# Game_Consol_Power.net
KiCad netlist of a schematic drawn in Altium Designer
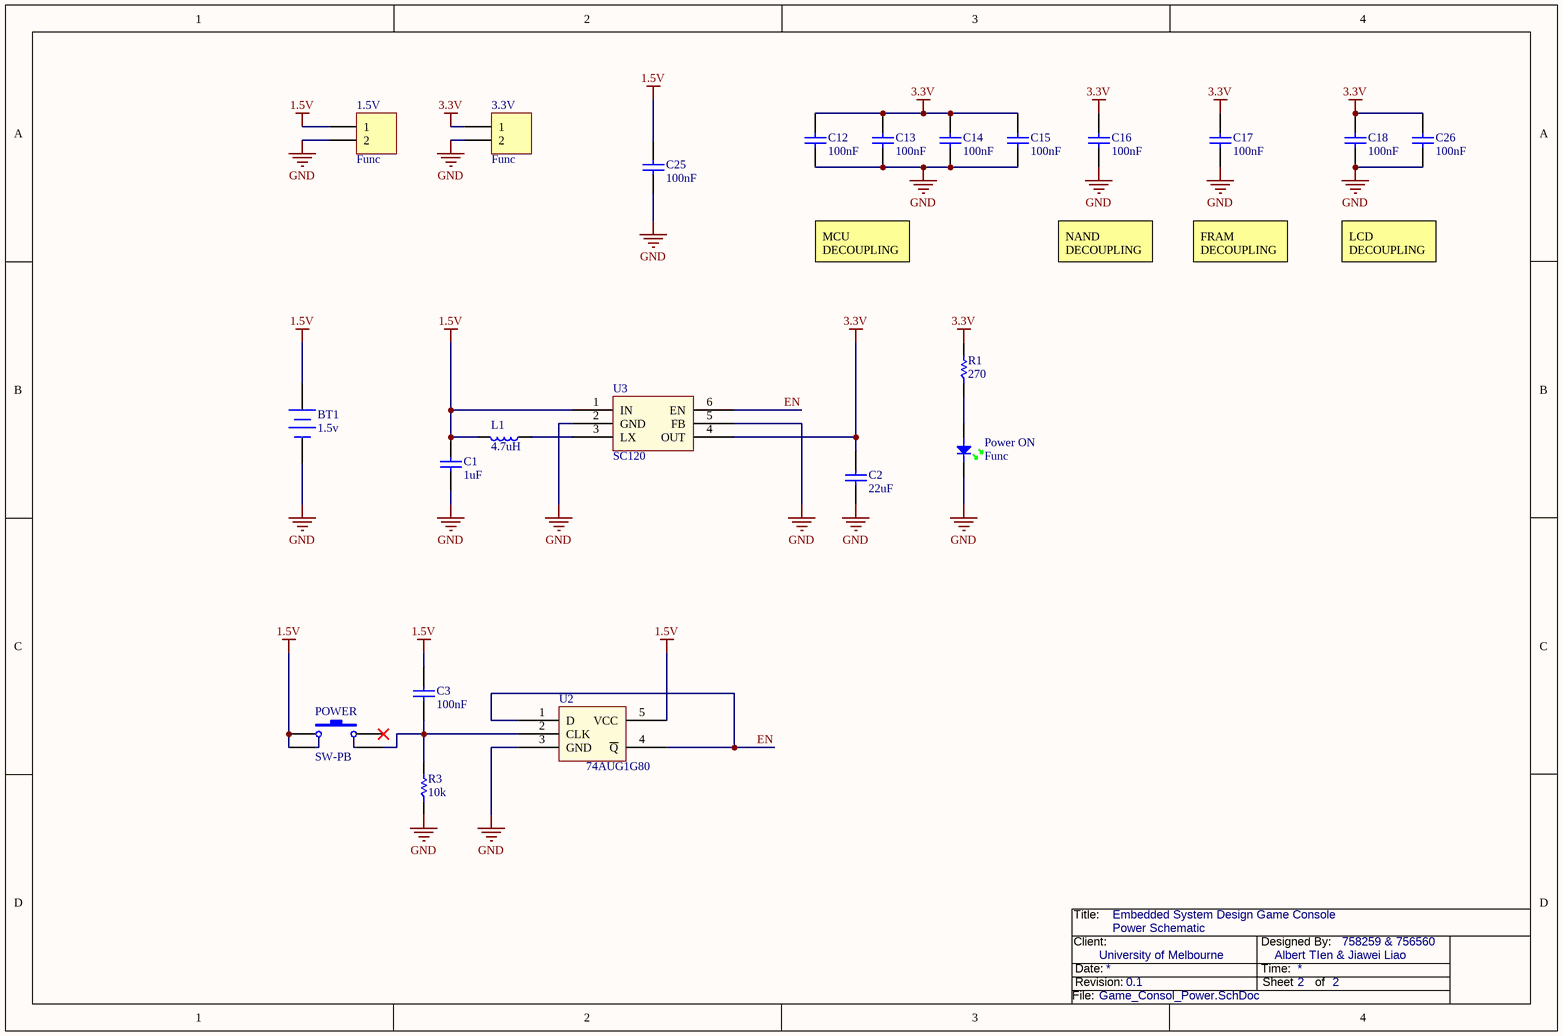
[diagram p0: Game_Consol_Power.SchDoc]

(export (version "E")
  (design (tool "Eeschema 10.0.6"))
  (components
    (comp (ref "1.5V")
      (value "Func")
      (footprint "HDR1X2")
      (description "2 Pin Header")
      (fields (field (name "PUBLISHER") "Altium Limited"))
      (libsource (lib "EmbSD Lib 0v1") (part "HDR2"))
    )
    (comp (ref "3.3V")
      (value "Func")
      (footprint "HDR1X2")
      (description "2 Pin Header")
      (fields (field (name "PUBLISHER") "Altium Limited"))
      (libsource (lib "EmbSD Lib 0v1") (part "HDR2"))
    )
    (comp (ref "BT1")
      (value "1.5v")
      (footprint "BATT_HOLDER")
      (description "Battery Holder AA 1.5v")
      (fields (field (name "PUBLISHER") "Altium Limited"))
      (libsource (lib "EmbSD Lib 0v1") (part "BAT"))
    )
    (comp (ref "C1")
      (value "1uF")
      (footprint "0805")
      (description "Capacitor 100nF")
      (libsource (lib "EmbSD Lib 0v1") (part "C 0805"))
    )
    (comp (ref "C2")
      (value "22uF")
      (footprint "1210")
      (description "Capacitor 22uF")
      (fields
        (field (name "MANUFACTURER") "Generic Components")
        (field (name "MANUFACTURER PART NUMBER") "LMK316F226ZL-T")
        (field (name "PUBLISHER") "Altium Limited")
      )
      (libsource (lib "EmbSD Lib 0v1") (part "C 1210"))
    )
    (comp (ref "C3")
      (value "100nF")
      (footprint "0805")
      (description "Capacitor 100nF")
      (libsource (lib "EmbSD Lib 0v1") (part "C 0805"))
    )
    (comp (ref "C12")
      (value "100nF")
      (footprint "0805")
      (description "Capacitor 100nF")
      (libsource (lib "EmbSD Lib 0v1") (part "C 0805"))
    )
    (comp (ref "C13")
      (value "100nF")
      (footprint "0805")
      (description "Capacitor 100nF")
      (libsource (lib "EmbSD Lib 0v1") (part "C 0805"))
    )
    (comp (ref "C14")
      (value "100nF")
      (footprint "0805")
      (description "Capacitor 100nF")
      (libsource (lib "EmbSD Lib 0v1") (part "C 0805"))
    )
    (comp (ref "C15")
      (value "100nF")
      (footprint "0805")
      (description "Capacitor 100nF")
      (libsource (lib "EmbSD Lib 0v1") (part "C 0805"))
    )
    (comp (ref "C16")
      (value "100nF")
      (footprint "0805")
      (description "Capacitor 100nF")
      (libsource (lib "EmbSD Lib 0v1") (part "C 0805"))
    )
    (comp (ref "C17")
      (value "100nF")
      (footprint "0805")
      (description "Capacitor 100nF")
      (libsource (lib "EmbSD Lib 0v1") (part "C 0805"))
    )
    (comp (ref "C18")
      (value "100nF")
      (footprint "0805")
      (description "Capacitor 100nF")
      (libsource (lib "EmbSD Lib 0v1") (part "C 0805"))
    )
    (comp (ref "C25")
      (value "100nF")
      (footprint "0805")
      (description "Capacitor 100nF")
      (libsource (lib "EmbSD Lib 0v1") (part "C 0805"))
    )
    (comp (ref "C26")
      (value "100nF")
      (footprint "0805")
      (description "Capacitor 100nF")
      (libsource (lib "EmbSD Lib 0v1") (part "C 0805"))
    )
    (comp (ref "L1")
      (value "4.7uH")
      (footprint "1210L")
      (description "Inductor 4.7uH")
      (fields
        (field (name "MANUFACTURER") "Murata Electronics North America")
        (field (name "MANUFACTURER PART NUMBER") "LQH32CN4R7M23L")
        (field (name "PUBLISHER") "Altium Limited")
      )
      (libsource (lib "EmbSD Lib 0v1") (part "I 1210"))
    )
    (comp (ref "POWER")
      (value "SW-PB")
      (footprint "SPNO_SMD")
      (description "Push Button Switch")
      (fields
        (field (name "MANUFACTURER") "TE Connectivity")
        (field (name "MANUFACTURER PART NUMBER") "FSM4JSMA")
        (field (name "PUBLISHER") "Altium Limited")
      )
      (libsource (lib "EmbSD Lib 0v1") (part "SW-PB"))
    )
    (comp (ref "Power ON")
      (value "Func")
      (footprint "0805D")
      (description "Light Emitting Diode")
      (fields (field (name "MANUFACTURER") "Generic Components") (field (name "PUBLISHER") "Altium Limited"))
      (libsource (lib "EmbSD Lib 0v1") (part "LED GREEN"))
    )
    (comp (ref "R1")
      (value "270")
      (footprint "0805")
      (description "Resistor")
      (libsource (lib "EmbSD Lib 0v1") (part "R"))
    )
    (comp (ref "R3")
      (value "10k")
      (footprint "0805")
      (description "Resistor")
      (libsource (lib "EmbSD Lib 0v1") (part "R"))
    )
    (comp (ref "U2")
      (value "74AUG1G80")
      (footprint "SOT23-5")
      (description "Inverted single D flip flop")
      (libsource (lib "EmbSD Lib 0v1") (part "74AUG1G80"))
    )
    (comp (ref "U3")
      (value "SC120")
      (footprint "SOT23-6")
      (description "Regulator Low Voltage")
      (libsource (lib "EmbSD Lib 0v1") (part "SC120"))
    )
  )
  (nets
    (net (code "1") (name "/EN") (class "Default")
      (node (ref "U2") (pin "1") (pinfunction "D_1") (pintype "passive"))
      (node (ref "U2") (pin "4") (pinfunction "~{Q}_4") (pintype "passive"))
      (node (ref "U3") (pin "6") (pinfunction "EN_6") (pintype "passive"))
    )
    (net (code "2") (name "1.5V") (class "Default")
      (node (ref "1.5V") (pin "1") (pinfunction "1_1") (pintype "passive"))
      (node (ref "BT1") (pin "1") (pinfunction "+_1") (pintype "passive"))
      (node (ref "C1") (pin "1") (pinfunction "1_1") (pintype "passive"))
      (node (ref "C25") (pin "1") (pinfunction "1_1") (pintype "passive"))
      (node (ref "C3") (pin "1") (pinfunction "1_1") (pintype "passive"))
      (node (ref "L1") (pin "2") (pinfunction "2_2") (pintype "passive"))
      (node (ref "POWER") (pin "1") (pinfunction "1_1") (pintype "passive"))
      (node (ref "POWER") (pin "2") (pinfunction "2_2") (pintype "passive"))
      (node (ref "U2") (pin "5") (pinfunction "VCC_5") (pintype "passive"))
      (node (ref "U3") (pin "1") (pinfunction "IN_1") (pintype "passive"))
    )
    (net (code "3") (name "3.3V") (class "Default")
      (node (ref "3.3V") (pin "1") (pinfunction "1_1") (pintype "passive"))
      (node (ref "C12") (pin "1") (pinfunction "1_1") (pintype "passive"))
      (node (ref "C13") (pin "1") (pinfunction "1_1") (pintype "passive"))
      (node (ref "C14") (pin "1") (pinfunction "1_1") (pintype "passive"))
      (node (ref "C15") (pin "1") (pinfunction "1_1") (pintype "passive"))
      (node (ref "C16") (pin "1") (pinfunction "1_1") (pintype "passive"))
      (node (ref "C17") (pin "1") (pinfunction "1_1") (pintype "passive"))
      (node (ref "C18") (pin "1") (pinfunction "1_1") (pintype "passive"))
      (node (ref "C2") (pin "1") (pinfunction "1_1") (pintype "passive"))
      (node (ref "C26") (pin "1") (pinfunction "1_1") (pintype "passive"))
      (node (ref "R1") (pin "2") (pintype "passive"))
      (node (ref "U3") (pin "4") (pinfunction "OUT_4") (pintype "passive"))
    )
    (net (code "4") (name "GND") (class "Default")
      (node (ref "1.5V") (pin "2") (pinfunction "2_2") (pintype "passive"))
      (node (ref "3.3V") (pin "2") (pinfunction "2_2") (pintype "passive"))
      (node (ref "BT1") (pin "2") (pinfunction "-_2") (pintype "passive"))
      (node (ref "C1") (pin "2") (pinfunction "2_2") (pintype "passive"))
      (node (ref "C12") (pin "2") (pinfunction "2_2") (pintype "passive"))
      (node (ref "C13") (pin "2") (pinfunction "2_2") (pintype "passive"))
      (node (ref "C14") (pin "2") (pinfunction "2_2") (pintype "passive"))
      (node (ref "C15") (pin "2") (pinfunction "2_2") (pintype "passive"))
      (node (ref "C16") (pin "2") (pinfunction "2_2") (pintype "passive"))
      (node (ref "C17") (pin "2") (pinfunction "2_2") (pintype "passive"))
      (node (ref "C18") (pin "2") (pinfunction "2_2") (pintype "passive"))
      (node (ref "C2") (pin "2") (pinfunction "2_2") (pintype "passive"))
      (node (ref "C25") (pin "2") (pinfunction "2_2") (pintype "passive"))
      (node (ref "C26") (pin "2") (pinfunction "2_2") (pintype "passive"))
      (node (ref "Power ON") (pin "K") (pinfunction "K_K") (pintype "passive"))
      (node (ref "R3") (pin "1") (pintype "passive"))
      (node (ref "U2") (pin "3") (pinfunction "GND_3") (pintype "passive"))
      (node (ref "U3") (pin "2") (pinfunction "GND_2") (pintype "passive"))
      (node (ref "U3") (pin "5") (pinfunction "FB_5") (pintype "passive"))
    )
    (net (code "5") (name "Net-(Power ON-PadA)") (class "Default")
      (node (ref "Power ON") (pin "A") (pinfunction "A_A") (pintype "passive"))
      (node (ref "R1") (pin "1") (pintype "passive"))
    )
    (net (code "6") (name "Net-(U2-CLK)") (class "Default")
      (node (ref "C3") (pin "2") (pinfunction "2_2") (pintype "passive"))
      (node (ref "POWER") (pin "4") (pinfunction "4_4") (pintype "passive"))
      (node (ref "R3") (pin "2") (pintype "passive"))
      (node (ref "U2") (pin "2") (pinfunction "CLK_2") (pintype "passive"))
    )
    (net (code "7") (name "Net-(U3-LX)") (class "Default")
      (node (ref "L1") (pin "1") (pinfunction "1_1") (pintype "passive"))
      (node (ref "U3") (pin "3") (pinfunction "LX_3") (pintype "passive"))
    )
    (net (code "8") (name "unconnected-(POWER-Pad3)") (class "Default")
      (node (ref "POWER") (pin "3") (pinfunction "3_3") (pintype "passive+no_connect"))
    )
  )
)
